# SingleLED-v1.net
KiCad netlist of a schematic drawn in EAGLE
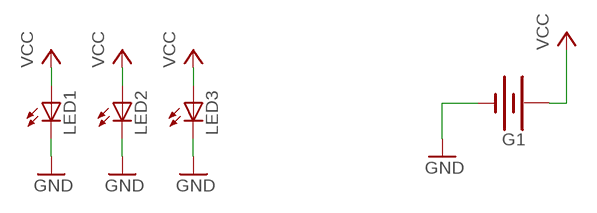
[diagram p0: schematic, sheet 1]

(export (version "E")
  (design (tool "Eeschema 10.0.6"))
  (components
    (comp (ref "G1")
      (value "BATTERY-20MM_PTH")
      (footprint "eagle-import:BATTCOM_20MM_PTH")
      (libsource (lib "eagle-import") (part "BATTERY-20MM_PTH"))
    )
    (comp (ref "LED1")
      (value "LED5MM")
      (footprint "eagle-import:LED5MM")
      (libsource (lib "eagle-import") (part "LED5MM"))
    )
    (comp (ref "LED2")
      (value "LED5MM")
      (footprint "eagle-import:LED5MM")
      (libsource (lib "eagle-import") (part "LED5MM"))
    )
    (comp (ref "LED3")
      (value "LED5MM")
      (footprint "eagle-import:LED5MM")
      (libsource (lib "eagle-import") (part "LED5MM"))
    )
  )
  (nets
    (net (code "1") (name "GND") (class "Default")
      (node (ref "G1") (pin "2") (pinfunction "-_2") (pintype "power_in"))
      (node (ref "LED1") (pin "K") (pinfunction "C_K") (pintype "passive"))
      (node (ref "LED2") (pin "K") (pinfunction "C_K") (pintype "passive"))
      (node (ref "LED3") (pin "K") (pinfunction "C_K") (pintype "passive"))
    )
    (net (code "2") (name "VCC") (class "Default")
      (node (ref "G1") (pin "1") (pinfunction "+_1") (pintype "power_in"))
      (node (ref "LED1") (pin "A") (pinfunction "A_A") (pintype "passive"))
      (node (ref "LED2") (pin "A") (pinfunction "A_A") (pintype "passive"))
      (node (ref "LED3") (pin "A") (pinfunction "A_A") (pintype "passive"))
    )
  )
)
